# SQR_FG_Digital.net
KiCad netlist of a schematic drawn in EAGLE
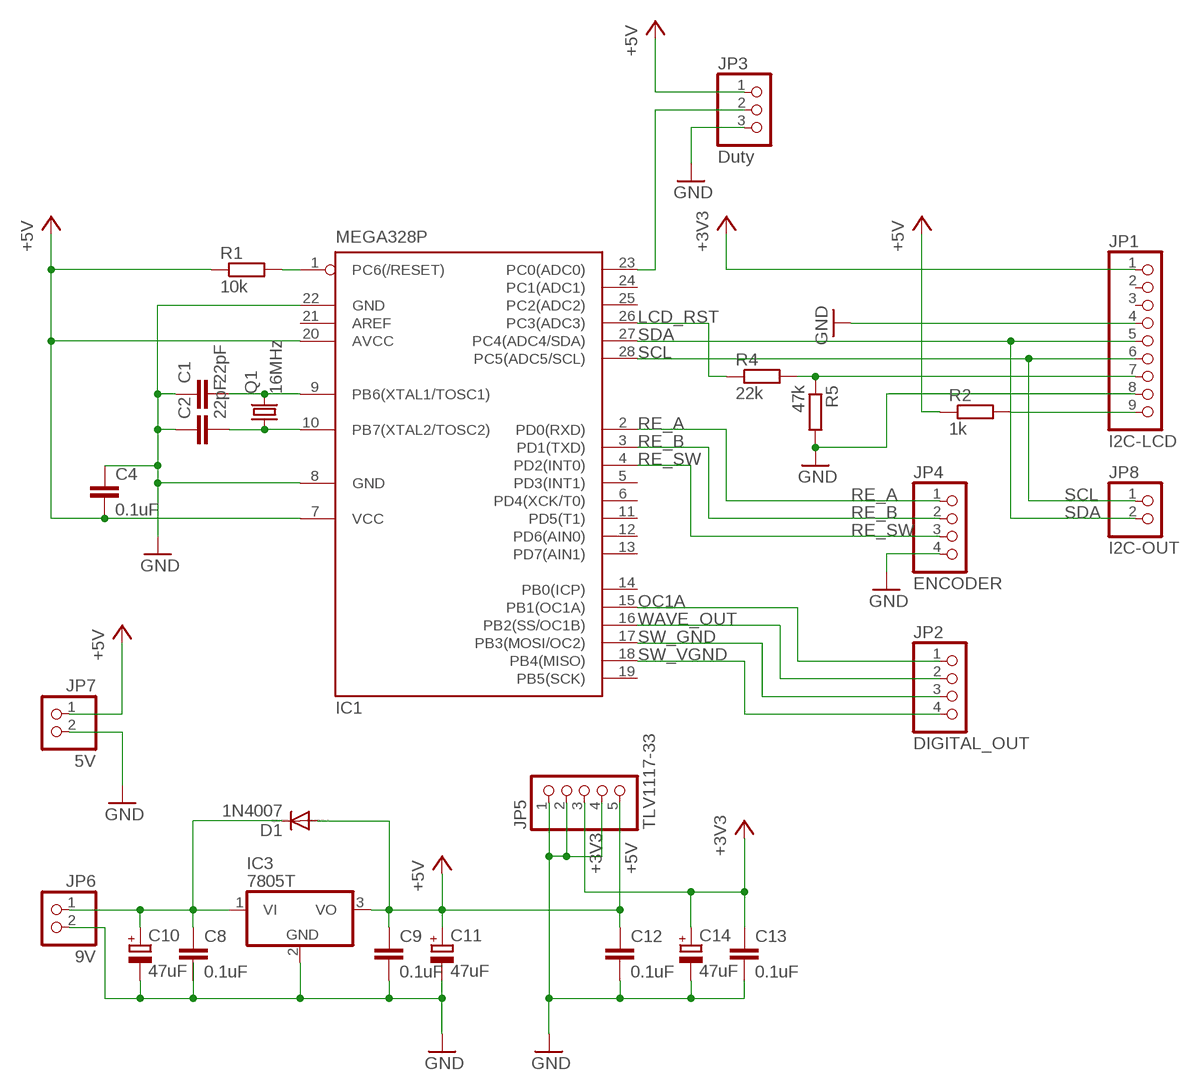
[diagram p0: schematic, sheet 1]

(export (version "E")
  (design (tool "Eeschema 10.0.6"))
  (components
    (comp (ref "C1")
      (value "22pF")
      (footprint "eagle-import:C050-024X044")
      (libsource (lib "eagle-import") (part "C-EU050-024X044"))
    )
    (comp (ref "C2")
      (value "22pF")
      (footprint "eagle-import:C050-024X044")
      (libsource (lib "eagle-import") (part "C-EU050-024X044"))
    )
    (comp (ref "C4")
      (value "0.1uF")
      (footprint "eagle-import:C025-024X044")
      (libsource (lib "eagle-import") (part "C-EU025-024X044"))
    )
    (comp (ref "C8")
      (value "0.1uF")
      (footprint "eagle-import:C025-024X044")
      (libsource (lib "eagle-import") (part "C-EU025-024X044"))
    )
    (comp (ref "C9")
      (value "0.1uF")
      (footprint "eagle-import:C025-024X044")
      (libsource (lib "eagle-import") (part "C-EU025-024X044"))
    )
    (comp (ref "C10")
      (value "47uF")
      (footprint "eagle-import:TT2D5L")
      (libsource (lib "eagle-import") (part "CPOL-EUTT2D5L"))
    )
    (comp (ref "C11")
      (value "47uF")
      (footprint "eagle-import:TT2D5L")
      (libsource (lib "eagle-import") (part "CPOL-EUTT2D5L"))
    )
    (comp (ref "C12")
      (value "0.1uF")
      (footprint "eagle-import:C025-024X044")
      (libsource (lib "eagle-import") (part "C-EU025-024X044"))
    )
    (comp (ref "C13")
      (value "0.1uF")
      (footprint "eagle-import:C025-024X044")
      (libsource (lib "eagle-import") (part "C-EU025-024X044"))
    )
    (comp (ref "C14")
      (value "47uF")
      (footprint "eagle-import:TT2D5L")
      (libsource (lib "eagle-import") (part "CPOL-EUTT2D5L"))
    )
    (comp (ref "D1")
      (value "1N4007")
      (footprint "eagle-import:DO41-10")
      (libsource (lib "eagle-import") (part "1N4004"))
    )
    (comp (ref "IC1")
      (value "MEGA328P")
      (footprint "eagle-import:DIL28-3")
      (libsource (lib "eagle-import") (part "MEGA8-P"))
    )
    (comp (ref "IC3")
      (value "7805T")
      (footprint "eagle-import:TO220H")
      (libsource (lib "eagle-import") (part "78T05"))
    )
    (comp (ref "JP1")
      (value "I2C-LCD")
      (footprint "eagle-import:1X09")
      (libsource (lib "eagle-import") (part "PINHD-1X9"))
    )
    (comp (ref "JP2")
      (value "DIGITAL_OUT")
      (footprint "eagle-import:1X04")
      (libsource (lib "eagle-import") (part "PINHD-1X4"))
    )
    (comp (ref "JP3")
      (value "Duty")
      (footprint "eagle-import:1X03")
      (libsource (lib "eagle-import") (part "PINHD-1X3"))
    )
    (comp (ref "JP4")
      (value "ENCODER")
      (footprint "eagle-import:1X04")
      (libsource (lib "eagle-import") (part "PINHD-1X4"))
    )
    (comp (ref "JP5")
      (value "TLV1117-33")
      (footprint "eagle-import:1X05")
      (libsource (lib "eagle-import") (part "PINHD-1X5"))
    )
    (comp (ref "JP6")
      (value "9V")
      (footprint "eagle-import:1X02")
      (libsource (lib "eagle-import") (part "PINHD-1X2"))
    )
    (comp (ref "JP7")
      (value "5V")
      (footprint "eagle-import:1X02")
      (libsource (lib "eagle-import") (part "PINHD-1X2"))
    )
    (comp (ref "JP8")
      (value "I2C-OUT")
      (footprint "eagle-import:1X02")
      (libsource (lib "eagle-import") (part "PINHD-1X2"))
    )
    (comp (ref "Q1")
      (value "16MHz")
      (footprint "eagle-import:HC49_S")
      (libsource (lib "eagle-import") (part "CRYSTALHC49S"))
    )
    (comp (ref "R1")
      (value "10k")
      (footprint "eagle-import:0207_10")
      (libsource (lib "eagle-import") (part "R-EU_0207/10"))
    )
    (comp (ref "R2")
      (value "1k")
      (footprint "eagle-import:0207_7")
      (libsource (lib "eagle-import") (part "R-EU_0207/7"))
    )
    (comp (ref "R4")
      (value "22k")
      (footprint "eagle-import:0207_7")
      (libsource (lib "eagle-import") (part "R-EU_0207/7"))
    )
    (comp (ref "R5")
      (value "47k")
      (footprint "eagle-import:0207_7")
      (libsource (lib "eagle-import") (part "R-EU_0207/7"))
    )
  )
  (nets
    (net (code "1") (name "+3V3") (class "Default")
      (node (ref "C13") (pin "1") (pinfunction "1_1") (pintype "passive"))
      (node (ref "C14") (pin "+") (pinfunction "+_+") (pintype "passive"))
      (node (ref "JP1") (pin "1") (pinfunction "1_1") (pintype "passive"))
      (node (ref "JP5") (pin "3") (pinfunction "3_3") (pintype "passive"))
    )
    (net (code "2") (name "+5V") (class "Default")
      (node (ref "C11") (pin "+") (pinfunction "+_+") (pintype "passive"))
      (node (ref "C12") (pin "1") (pinfunction "1_1") (pintype "passive"))
      (node (ref "C4") (pin "2") (pinfunction "2_2") (pintype "passive"))
      (node (ref "C9") (pin "1") (pinfunction "1_1") (pintype "passive"))
      (node (ref "D1") (pin "A") (pinfunction "A_A") (pintype "passive"))
      (node (ref "IC1") (pin "20") (pinfunction "AVCC_20") (pintype "power_in"))
      (node (ref "IC1") (pin "7") (pinfunction "VCC_7") (pintype "power_in"))
      (node (ref "IC3") (pin "3") (pinfunction "VO_3") (pintype "passive"))
      (node (ref "JP3") (pin "1") (pinfunction "1_1") (pintype "passive"))
      (node (ref "JP5") (pin "5") (pinfunction "5_5") (pintype "passive"))
      (node (ref "JP7") (pin "1") (pinfunction "1_1") (pintype "passive"))
      (node (ref "R1") (pin "1") (pinfunction "1_1") (pintype "passive"))
      (node (ref "R2") (pin "1") (pinfunction "1_1") (pintype "passive"))
    )
    (net (code "3") (name "/LCD_RST") (class "Default")
      (node (ref "IC1") (pin "26") (pinfunction "PC3(ADC3)_26") (pintype "bidirectional"))
      (node (ref "R4") (pin "1") (pinfunction "1_1") (pintype "passive"))
    )
    (net (code "4") (name "/OC1A") (class "Default")
      (node (ref "IC1") (pin "15") (pinfunction "PB1(OC1A)_15") (pintype "bidirectional"))
      (node (ref "JP2") (pin "1") (pinfunction "1_1") (pintype "passive"))
    )
    (net (code "5") (name "/RE_A") (class "Default")
      (node (ref "IC1") (pin "2") (pinfunction "PD0(RXD)_2") (pintype "bidirectional"))
      (node (ref "JP4") (pin "1") (pinfunction "1_1") (pintype "passive"))
    )
    (net (code "6") (name "/RE_B") (class "Default")
      (node (ref "IC1") (pin "3") (pinfunction "PD1(TXD)_3") (pintype "bidirectional"))
      (node (ref "JP4") (pin "2") (pinfunction "2_2") (pintype "passive"))
    )
    (net (code "7") (name "/RE_SW") (class "Default")
      (node (ref "IC1") (pin "4") (pinfunction "PD2(INT0)_4") (pintype "bidirectional"))
      (node (ref "JP4") (pin "3") (pinfunction "3_3") (pintype "passive"))
    )
    (net (code "8") (name "/SCL") (class "Default")
      (node (ref "IC1") (pin "28") (pinfunction "PC5(ADC5/SCL)_28") (pintype "bidirectional"))
      (node (ref "JP1") (pin "6") (pinfunction "6_6") (pintype "passive"))
      (node (ref "JP8") (pin "1") (pinfunction "1_1") (pintype "passive"))
    )
    (net (code "9") (name "/SDA") (class "Default")
      (node (ref "IC1") (pin "27") (pinfunction "PC4(ADC4/SDA)_27") (pintype "bidirectional"))
      (node (ref "JP1") (pin "5") (pinfunction "5_5") (pintype "passive"))
      (node (ref "JP8") (pin "2") (pinfunction "2_2") (pintype "passive"))
    )
    (net (code "10") (name "/SW_GND") (class "Default")
      (node (ref "IC1") (pin "17") (pinfunction "PB3(MOSI/OC2)_17") (pintype "bidirectional"))
      (node (ref "JP2") (pin "3") (pinfunction "3_3") (pintype "passive"))
    )
    (net (code "11") (name "/SW_VGND") (class "Default")
      (node (ref "IC1") (pin "18") (pinfunction "PB4(MISO)_18") (pintype "bidirectional"))
      (node (ref "JP2") (pin "4") (pinfunction "4_4") (pintype "passive"))
    )
    (net (code "12") (name "/WAVE_OUT") (class "Default")
      (node (ref "IC1") (pin "16") (pinfunction "PB2(SS/OC1B)_16") (pintype "bidirectional"))
      (node (ref "JP2") (pin "2") (pinfunction "2_2") (pintype "passive"))
    )
    (net (code "13") (name "GND") (class "Default")
      (node (ref "C1") (pin "1") (pinfunction "1_1") (pintype "passive"))
      (node (ref "C10") (pin "-") (pinfunction "-_-") (pintype "passive"))
      (node (ref "C11") (pin "-") (pinfunction "-_-") (pintype "passive"))
      (node (ref "C12") (pin "2") (pinfunction "2_2") (pintype "passive"))
      (node (ref "C13") (pin "2") (pinfunction "2_2") (pintype "passive"))
      (node (ref "C14") (pin "-") (pinfunction "-_-") (pintype "passive"))
      (node (ref "C2") (pin "1") (pinfunction "1_1") (pintype "passive"))
      (node (ref "C4") (pin "1") (pinfunction "1_1") (pintype "passive"))
      (node (ref "C8") (pin "2") (pinfunction "2_2") (pintype "passive"))
      (node (ref "C9") (pin "2") (pinfunction "2_2") (pintype "passive"))
      (node (ref "IC1") (pin "22") (pinfunction "GND_22") (pintype "power_in"))
      (node (ref "IC1") (pin "8") (pinfunction "GND_8") (pintype "power_in"))
      (node (ref "IC3") (pin "2") (pinfunction "GND_2") (pintype "passive"))
      (node (ref "JP1") (pin "4") (pinfunction "4_4") (pintype "passive"))
      (node (ref "JP1") (pin "8") (pinfunction "8_8") (pintype "passive"))
      (node (ref "JP3") (pin "3") (pinfunction "3_3") (pintype "passive"))
      (node (ref "JP4") (pin "4") (pinfunction "4_4") (pintype "passive"))
      (node (ref "JP5") (pin "1") (pinfunction "1_1") (pintype "passive"))
      (node (ref "JP5") (pin "2") (pinfunction "2_2") (pintype "passive"))
      (node (ref "JP5") (pin "4") (pinfunction "4_4") (pintype "passive"))
      (node (ref "JP6") (pin "2") (pinfunction "2_2") (pintype "passive"))
      (node (ref "JP7") (pin "2") (pinfunction "2_2") (pintype "passive"))
      (node (ref "R5") (pin "2") (pinfunction "2_2") (pintype "passive"))
    )
    (net (code "14") (name "Net-(IC1-PB6(XTAL1{slash}TOSC1))") (class "Default")
      (node (ref "C1") (pin "2") (pinfunction "2_2") (pintype "passive"))
      (node (ref "IC1") (pin "9") (pinfunction "PB6(XTAL1/TOSC1)_9") (pintype "bidirectional"))
      (node (ref "Q1") (pin "2") (pinfunction "2_2") (pintype "passive"))
    )
    (net (code "15") (name "Net-(IC1-PB7(XTAL2{slash}TOSC2))") (class "Default")
      (node (ref "C2") (pin "2") (pinfunction "2_2") (pintype "passive"))
      (node (ref "IC1") (pin "10") (pinfunction "PB7(XTAL2/TOSC2)_10") (pintype "bidirectional"))
      (node (ref "Q1") (pin "1") (pinfunction "1_1") (pintype "passive"))
    )
    (net (code "16") (name "Net-(IC1-PC0(ADC0))") (class "Default")
      (node (ref "IC1") (pin "23") (pinfunction "PC0(ADC0)_23") (pintype "bidirectional"))
      (node (ref "JP3") (pin "2") (pinfunction "2_2") (pintype "passive"))
    )
    (net (code "17") (name "Net-(IC1-PC6({slash}RESET))") (class "Default")
      (node (ref "IC1") (pin "1") (pinfunction "PC6(/RESET)_1") (pintype "bidirectional"))
      (node (ref "R1") (pin "2") (pinfunction "2_2") (pintype "passive"))
    )
    (net (code "18") (name "Net-(IC3-VI)") (class "Default")
      (node (ref "C10") (pin "+") (pinfunction "+_+") (pintype "passive"))
      (node (ref "C8") (pin "1") (pinfunction "1_1") (pintype "passive"))
      (node (ref "D1") (pin "C") (pinfunction "C_C") (pintype "passive"))
      (node (ref "IC3") (pin "1") (pinfunction "VI_1") (pintype "input"))
      (node (ref "JP6") (pin "1") (pinfunction "1_1") (pintype "passive"))
    )
    (net (code "19") (name "Net-(JP1-Pad7)") (class "Default")
      (node (ref "JP1") (pin "7") (pinfunction "7_7") (pintype "passive"))
      (node (ref "R4") (pin "2") (pinfunction "2_2") (pintype "passive"))
      (node (ref "R5") (pin "1") (pinfunction "1_1") (pintype "passive"))
    )
    (net (code "20") (name "Net-(JP1-Pad9)") (class "Default")
      (node (ref "JP1") (pin "9") (pinfunction "9_9") (pintype "passive"))
      (node (ref "R2") (pin "2") (pinfunction "2_2") (pintype "passive"))
    )
    (net (code "21") (name "unconnected-(IC1-AREF-Pad21)") (class "Default")
      (node (ref "IC1") (pin "21") (pinfunction "AREF_21") (pintype "passive"))
    )
    (net (code "22") (name "unconnected-(IC1-PB0(ICP)-Pad14)") (class "Default")
      (node (ref "IC1") (pin "14") (pinfunction "PB0(ICP)_14") (pintype "bidirectional"))
    )
    (net (code "23") (name "unconnected-(IC1-PB5(SCK)-Pad19)") (class "Default")
      (node (ref "IC1") (pin "19") (pinfunction "PB5(SCK)_19") (pintype "bidirectional"))
    )
    (net (code "24") (name "unconnected-(IC1-PC1(ADC1)-Pad24)") (class "Default")
      (node (ref "IC1") (pin "24") (pinfunction "PC1(ADC1)_24") (pintype "bidirectional"))
    )
    (net (code "25") (name "unconnected-(IC1-PC2(ADC2)-Pad25)") (class "Default")
      (node (ref "IC1") (pin "25") (pinfunction "PC2(ADC2)_25") (pintype "bidirectional"))
    )
    (net (code "26") (name "unconnected-(IC1-PD3(INT1)-Pad5)") (class "Default")
      (node (ref "IC1") (pin "5") (pinfunction "PD3(INT1)_5") (pintype "bidirectional"))
    )
    (net (code "27") (name "unconnected-(IC1-PD4(XCK{slash}T0)-Pad6)") (class "Default")
      (node (ref "IC1") (pin "6") (pinfunction "PD4(XCK/T0)_6") (pintype "bidirectional"))
    )
    (net (code "28") (name "unconnected-(IC1-PD5(T1)-Pad11)") (class "Default")
      (node (ref "IC1") (pin "11") (pinfunction "PD5(T1)_11") (pintype "bidirectional"))
    )
    (net (code "29") (name "unconnected-(IC1-PD6(AIN0)-Pad12)") (class "Default")
      (node (ref "IC1") (pin "12") (pinfunction "PD6(AIN0)_12") (pintype "bidirectional"))
    )
    (net (code "30") (name "unconnected-(IC1-PD7(AIN1)-Pad13)") (class "Default")
      (node (ref "IC1") (pin "13") (pinfunction "PD7(AIN1)_13") (pintype "bidirectional"))
    )
    (net (code "31") (name "unconnected-(JP1-Pad2)") (class "Default")
      (node (ref "JP1") (pin "2") (pinfunction "2_2") (pintype "passive"))
    )
    (net (code "32") (name "unconnected-(JP1-Pad3)") (class "Default")
      (node (ref "JP1") (pin "3") (pinfunction "3_3") (pintype "passive"))
    )
  )
)
